# Main.net
KiCad netlist of a schematic drawn in Altium Designer
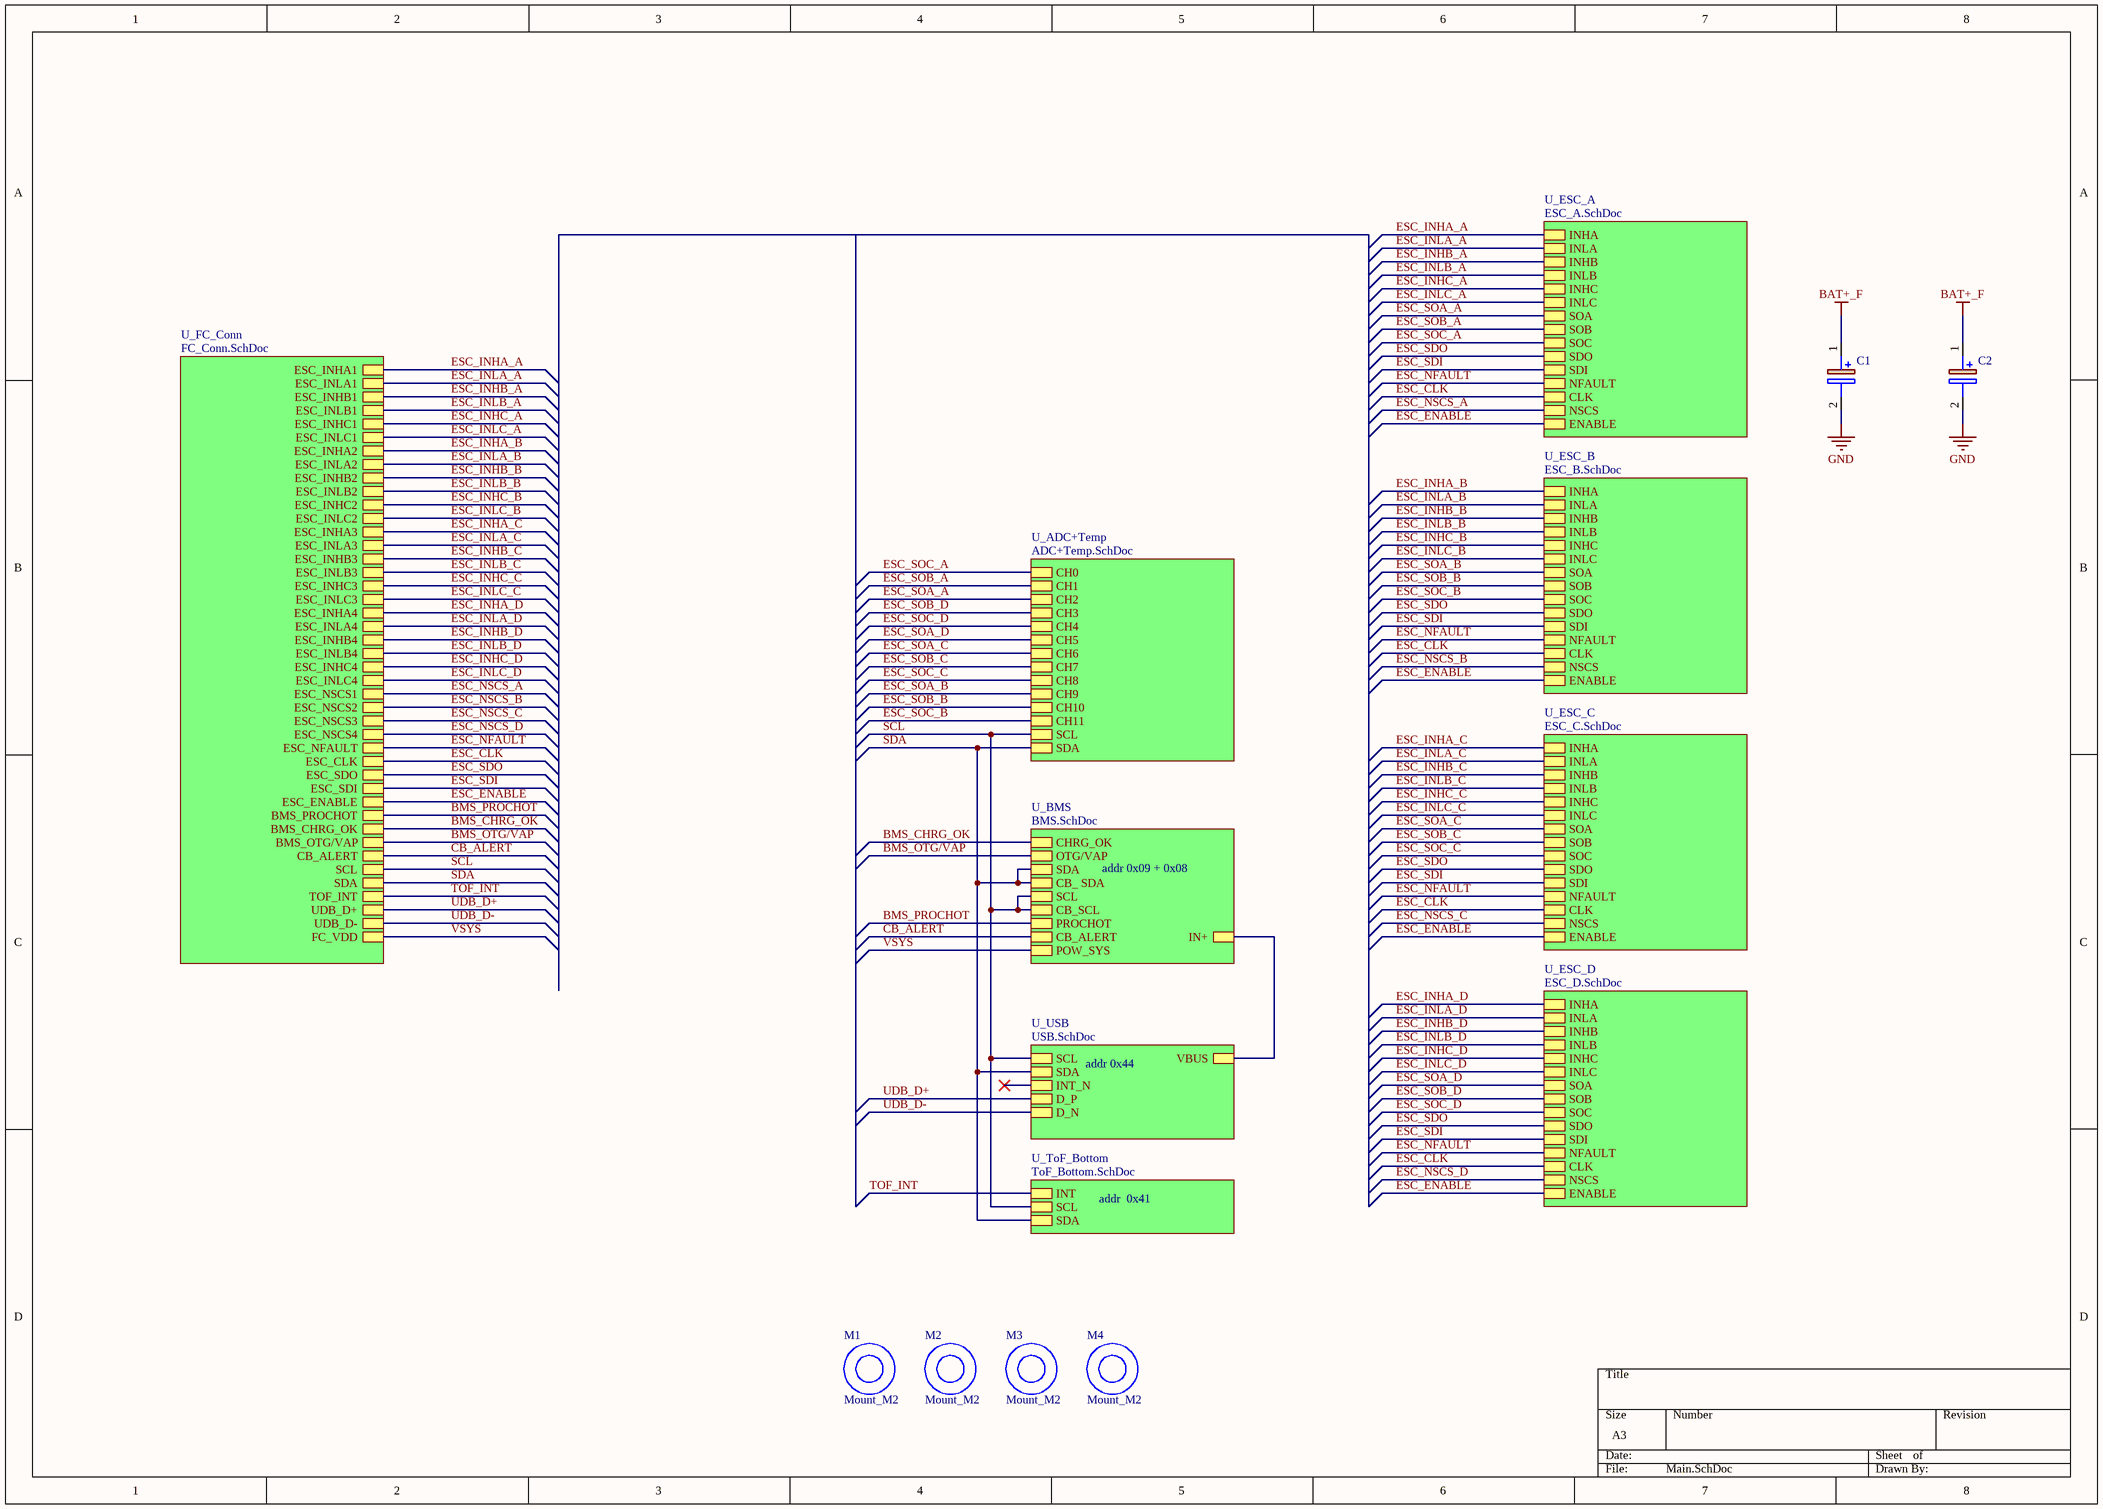
[diagram p0: Main.SchDoc]

(export (version "E")
  (design (tool "Eeschema 10.0.6"))
  (components
    (comp (ref "C1")
      (value "EEH-ZL1V151XP")
      (footprint "SamacSys:EEEHP1H4R7P")
      (description "Capacitor Polarised")
      (libsource (lib "*") (part "EEH-ZL1V151XP"))
    )
    (comp (ref "C2")
      (value "EEH-ZL1V151XP")
      (footprint "SamacSys:EEEHP1H4R7P")
      (description "Capacitor Polarised")
      (libsource (lib "*") (part "EEH-ZL1V151XP"))
    )
    (comp (ref "M1")
      (value "Mount_M2")
      (footprint "SamacSys:Mount_M2_anti_vibration_rubber")
      (libsource (lib "SamacSys") (part "Mount_M2"))
    )
    (comp (ref "M2")
      (value "Mount_M2")
      (footprint "SamacSys:Mount_M2_anti_vibration_rubber")
      (libsource (lib "SamacSys") (part "Mount_M2"))
    )
    (comp (ref "M3")
      (value "Mount_M2")
      (footprint "SamacSys:Mount_M2_anti_vibration_rubber")
      (libsource (lib "SamacSys") (part "Mount_M2"))
    )
    (comp (ref "M4")
      (value "Mount_M2")
      (footprint "SamacSys:Mount_M2_anti_vibration_rubber")
      (libsource (lib "SamacSys") (part "Mount_M2"))
    )
  )
  (nets
    (net (code "58") (name "BAT+_F") (class "Default")
      (node (ref "C1") (pin "1") (pinfunction "+_1") (pintype "passive"))
      (node (ref "C2") (pin "1") (pinfunction "+_1") (pintype "passive"))
    )
    (net (code "59") (name "GND") (class "Default")
      (node (ref "C1") (pin "2") (pinfunction "-_2") (pintype "passive"))
      (node (ref "C2") (pin "2") (pinfunction "-_2") (pintype "passive"))
    )
  )
)
